# MRCS-CMRI-CMRINet-Adapter.net
KiCad netlist of a schematic drawn in EAGLE
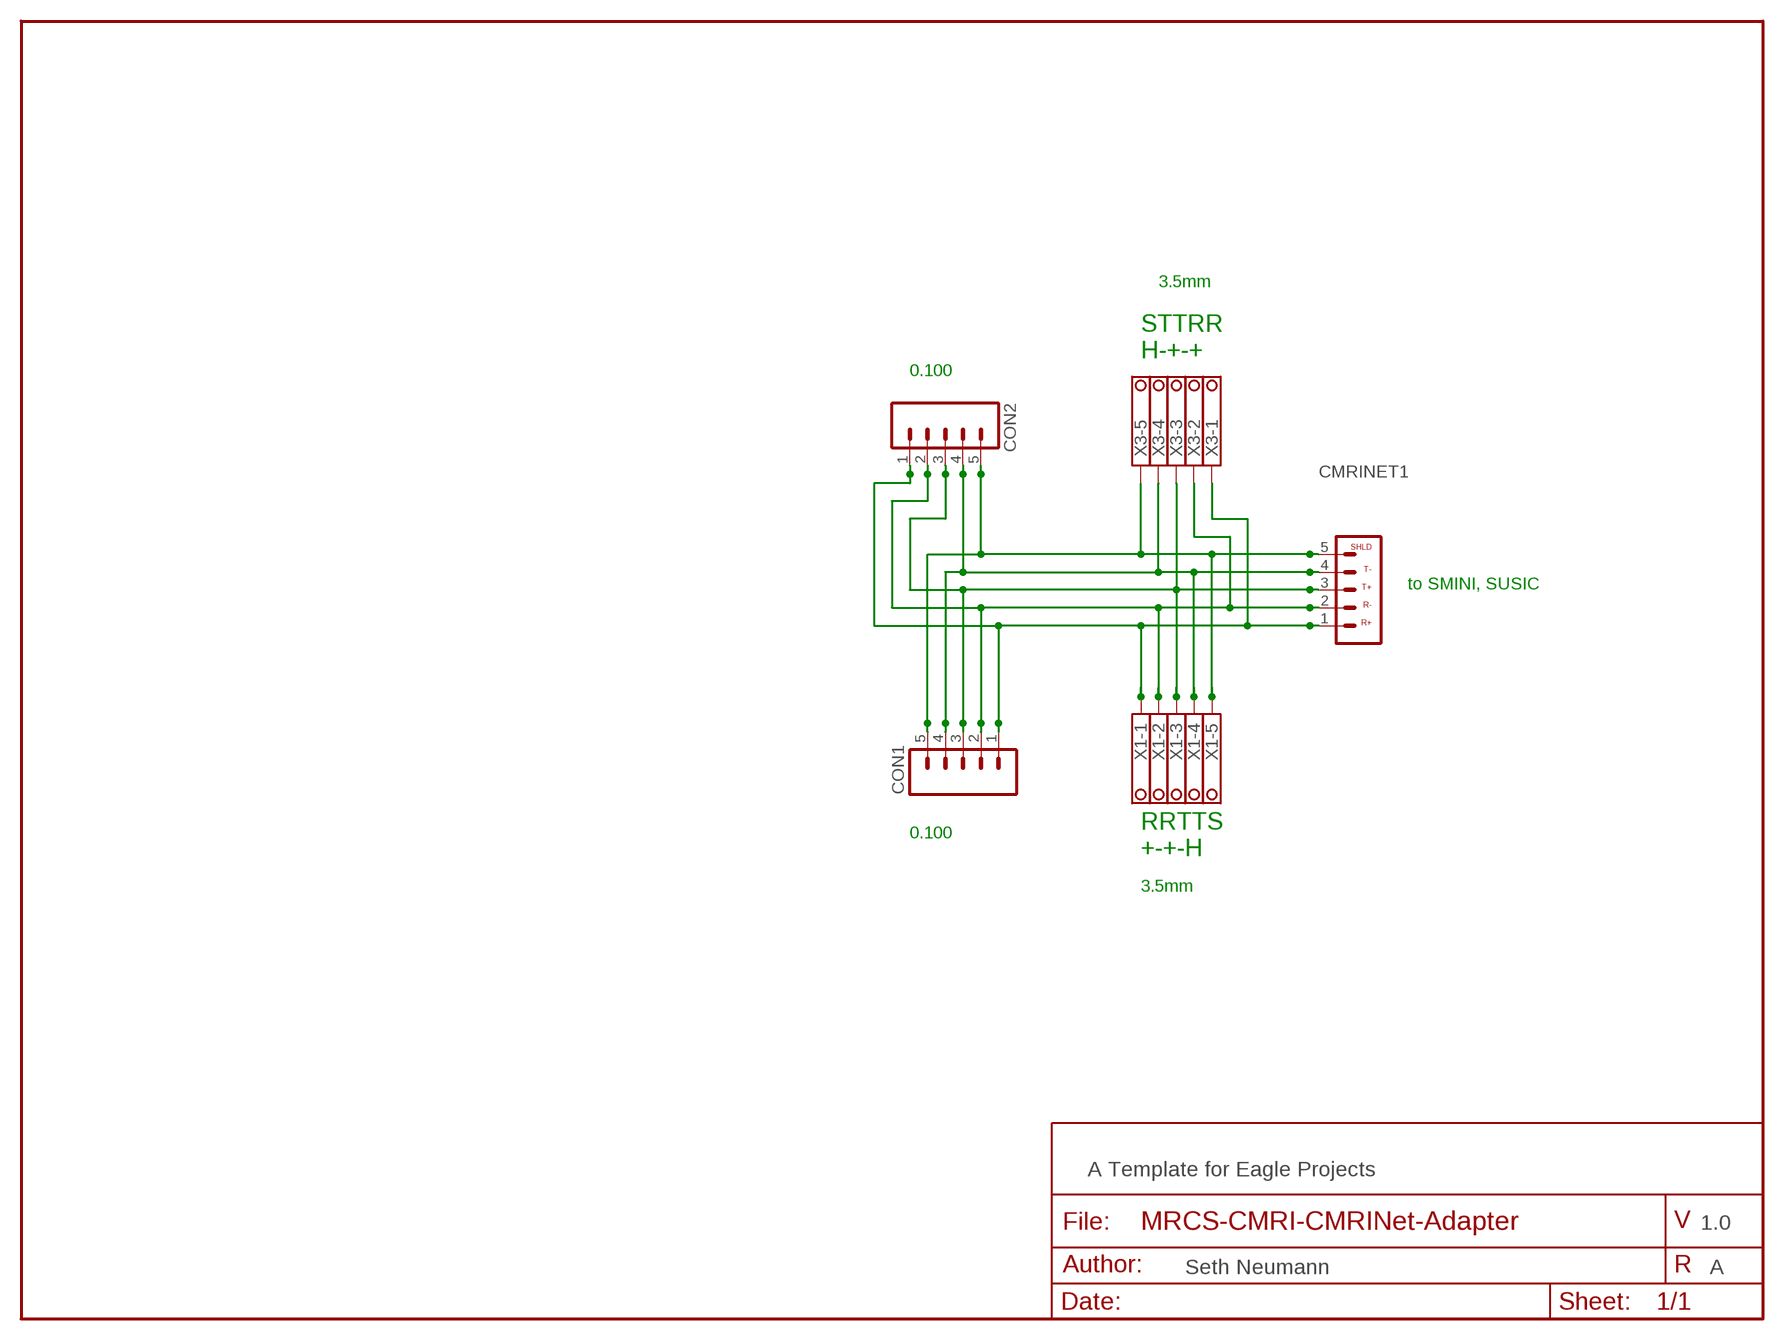
[diagram p0: schematic, sheet 1]

(export (version "E")
  (design (tool "Eeschema 10.0.6"))
  (components
    (comp (ref "CMRINET1")
      (value "CONNECTOR-CMRINET.156")
      (footprint "eagle-import:KK-156-5")
      (libsource (lib "eagle-import") (part "CONNECTOR-CMRINET.156"))
    )
    (comp (ref "CON1")
      (value "CONNECTOR-M05LOCK")
      (footprint "eagle-import:1X05_LOCK")
      (libsource (lib "eagle-import") (part "CONNECTOR-M05LOCK"))
    )
    (comp (ref "CON2")
      (value "CONNECTOR-M05LOCK")
      (footprint "eagle-import:1X05_LOCK")
      (libsource (lib "eagle-import") (part "CONNECTOR-M05LOCK"))
    )
    (comp (ref "X1")
      (value "1751277")
      (footprint "eagle-import:1751277")
      (libsource (lib "eagle-import") (part "1751277"))
    )
    (comp (ref "X3")
      (value "1751277")
      (footprint "eagle-import:1751277")
      (libsource (lib "eagle-import") (part "1751277"))
    )
  )
  (nets
    (net (code "1") (name "Net-(X1A-K)") (class "Default")
      (node (ref "CMRINET1") (pin "1") (pinfunction "1_1") (pintype "passive"))
      (node (ref "CON1") (pin "1") (pinfunction "1_1") (pintype "passive"))
      (node (ref "CON2") (pin "1") (pinfunction "1_1") (pintype "passive"))
      (node (ref "X1") (pin "1") (pinfunction "K_1") (pintype "passive"))
      (node (ref "X3") (pin "1") (pinfunction "K_1") (pintype "passive"))
    )
    (net (code "2") (name "Net-(X1B-K)") (class "Default")
      (node (ref "CMRINET1") (pin "2") (pinfunction "2_2") (pintype "passive"))
      (node (ref "CON1") (pin "2") (pinfunction "2_2") (pintype "passive"))
      (node (ref "CON2") (pin "2") (pinfunction "2_2") (pintype "passive"))
      (node (ref "X1") (pin "2") (pinfunction "K_2") (pintype "passive"))
      (node (ref "X3") (pin "2") (pinfunction "K_2") (pintype "passive"))
    )
    (net (code "3") (name "Net-(X1C-K)") (class "Default")
      (node (ref "CMRINET1") (pin "3") (pinfunction "3_3") (pintype "passive"))
      (node (ref "CON1") (pin "3") (pinfunction "3_3") (pintype "passive"))
      (node (ref "CON2") (pin "3") (pinfunction "3_3") (pintype "passive"))
      (node (ref "X1") (pin "3") (pinfunction "K_3") (pintype "passive"))
      (node (ref "X3") (pin "3") (pinfunction "K_3") (pintype "passive"))
    )
    (net (code "4") (name "Net-(X1D-K)") (class "Default")
      (node (ref "CMRINET1") (pin "4") (pinfunction "4_4") (pintype "passive"))
      (node (ref "CON1") (pin "4") (pinfunction "4_4") (pintype "passive"))
      (node (ref "CON2") (pin "4") (pinfunction "4_4") (pintype "passive"))
      (node (ref "X1") (pin "4") (pinfunction "K_4") (pintype "passive"))
      (node (ref "X3") (pin "4") (pinfunction "K_4") (pintype "passive"))
    )
    (net (code "5") (name "Net-(X1E-K)") (class "Default")
      (node (ref "CMRINET1") (pin "5") (pinfunction "5_5") (pintype "passive"))
      (node (ref "CON1") (pin "5") (pinfunction "5_5") (pintype "passive"))
      (node (ref "CON2") (pin "5") (pinfunction "5_5") (pintype "passive"))
      (node (ref "X1") (pin "5") (pinfunction "K_5") (pintype "passive"))
      (node (ref "X3") (pin "5") (pinfunction "K_5") (pintype "passive"))
    )
  )
)
